# Tempatroller.net
KiCad netlist of a schematic drawn in EAGLE
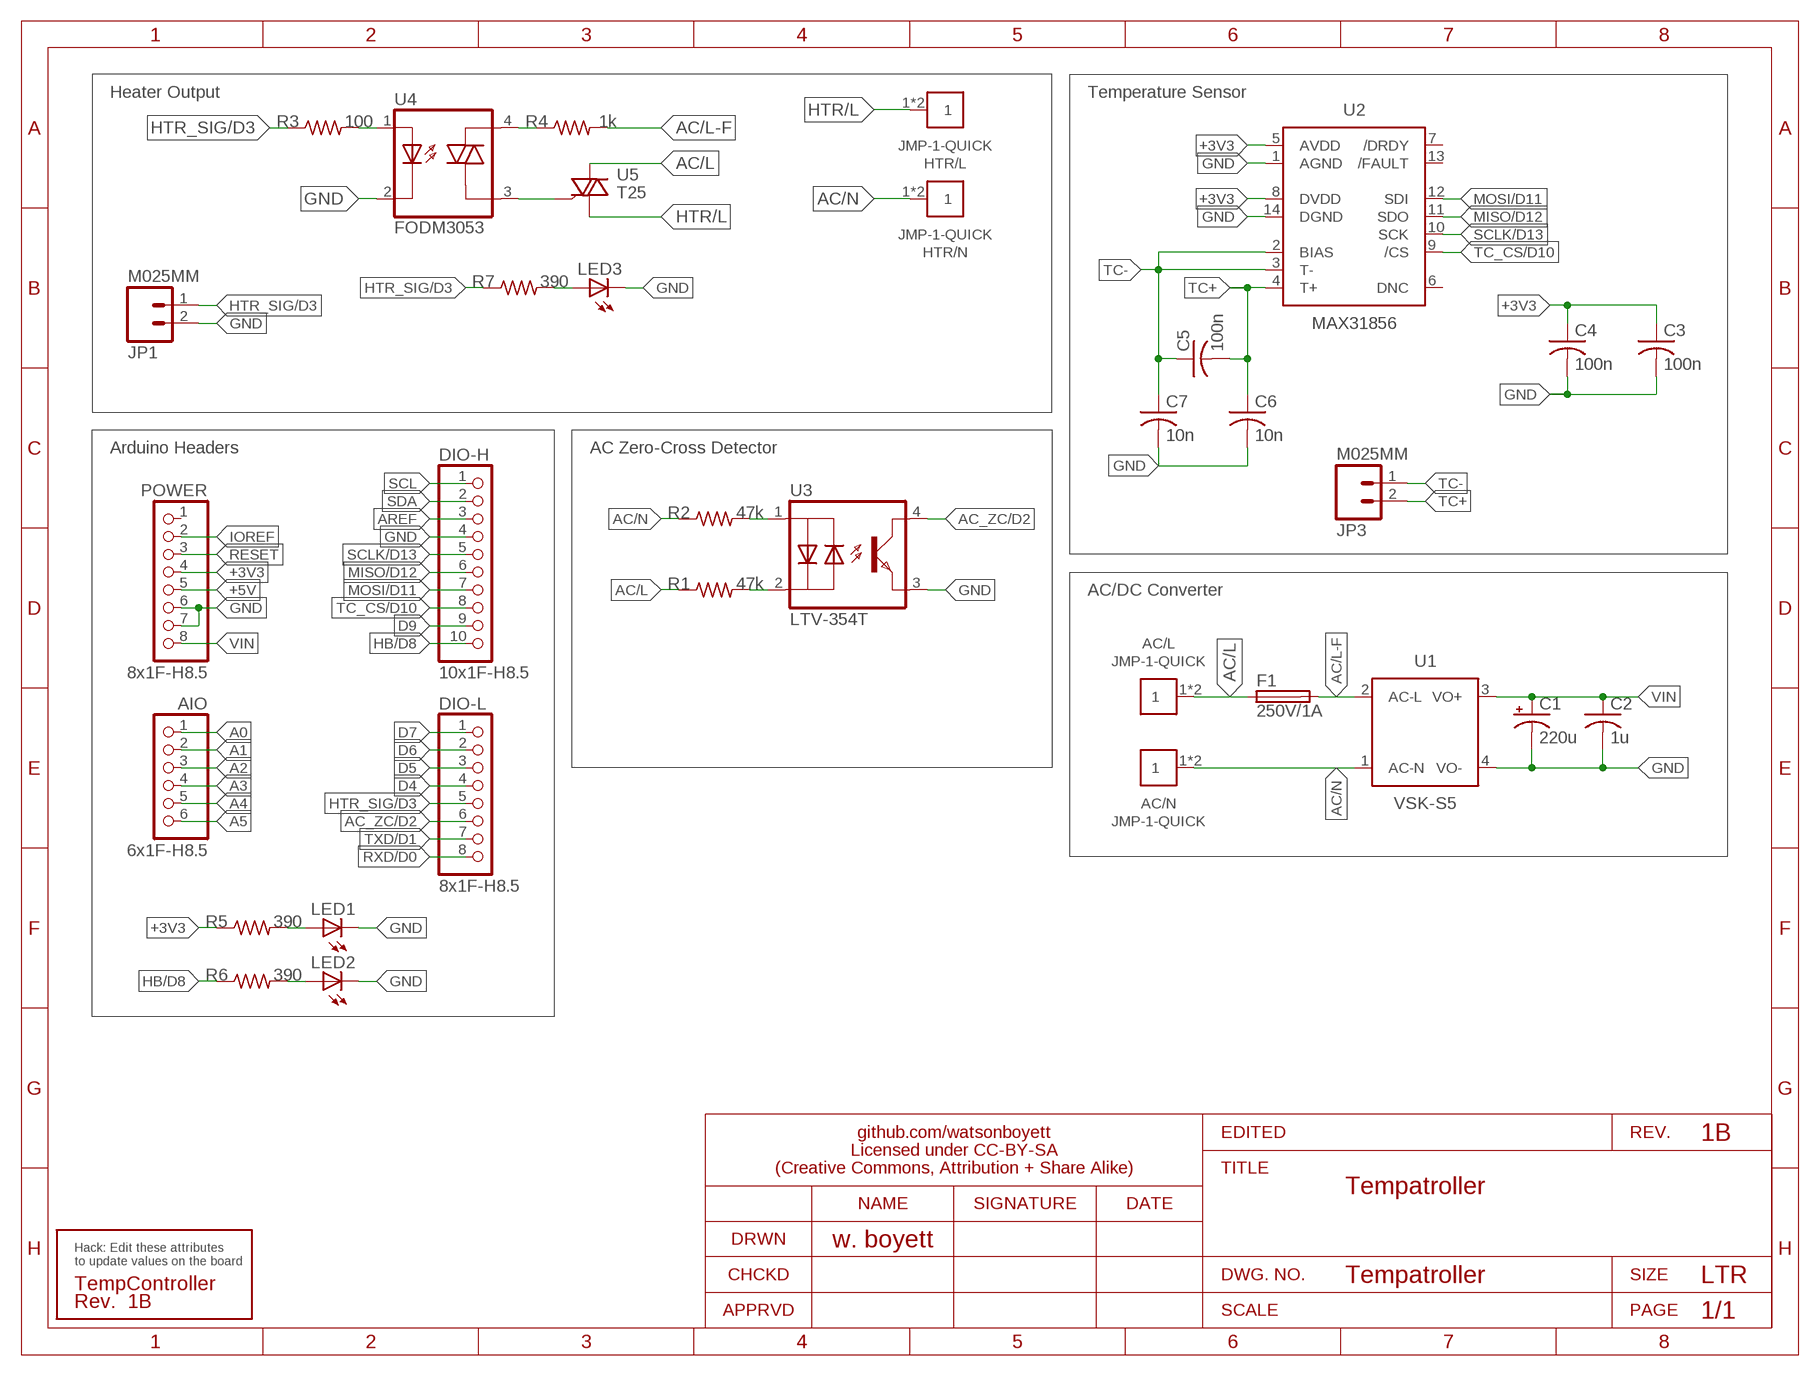
[diagram p0: schematic, sheet 1]

(export (version "E")
  (design (tool "Eeschema 10.0.6"))
  (components
    (comp (ref "AC/L")
      (value "JMP-1-QUICK")
      (footprint "eagle-import:QUICK-1")
      (fields (field (name "MPN") "1287"))
      (libsource (lib "eagle-import") (part "JMP-1-QUICK"))
    )
    (comp (ref "AC/N")
      (value "JMP-1-QUICK")
      (footprint "eagle-import:QUICK-1")
      (fields (field (name "MPN") "1287"))
      (libsource (lib "eagle-import") (part "JMP-1-QUICK"))
    )
    (comp (ref "AIO")
      (value "6x1F-H8.5")
      (footprint "eagle-import:1X06")
      (libsource (lib "eagle-import") (part "PINHD-1X6TH"))
    )
    (comp (ref "C1")
      (value "220u")
      (footprint "eagle-import:153CLV-1014")
      (libsource (lib "eagle-import") (part "CPOL-US153CLV-1014"))
    )
    (comp (ref "C2")
      (value "1u")
      (footprint "eagle-import:C0805")
      (libsource (lib "eagle-import") (part "C-USC0805"))
    )
    (comp (ref "C3")
      (value "100n")
      (footprint "eagle-import:C0805")
      (libsource (lib "eagle-import") (part "C-USC0805"))
    )
    (comp (ref "C4")
      (value "100n")
      (footprint "eagle-import:C0805")
      (libsource (lib "eagle-import") (part "C-USC0805"))
    )
    (comp (ref "C5")
      (value "100n")
      (footprint "eagle-import:C0805")
      (libsource (lib "eagle-import") (part "C-USC0805"))
    )
    (comp (ref "C6")
      (value "10n")
      (footprint "eagle-import:C0805")
      (libsource (lib "eagle-import") (part "C-USC0805"))
    )
    (comp (ref "C7")
      (value "10n")
      (footprint "eagle-import:C0805")
      (libsource (lib "eagle-import") (part "C-USC0805"))
    )
    (comp (ref "DIO-H")
      (value "10x1F-H8.5")
      (footprint "eagle-import:1X10")
      (libsource (lib "eagle-import") (part "PINHD-1X10TH"))
    )
    (comp (ref "DIO-L")
      (value "8x1F-H8.5")
      (footprint "eagle-import:1X08")
      (libsource (lib "eagle-import") (part "PINHD-1X8TH"))
    )
    (comp (ref "F1")
      (value "250V/1A")
      (footprint "eagle-import:2SMD-2410")
      (fields
        (field (name "MPN") "0452004.MRL")
        (field (name "MPN_1") "0454001.MR")
        (field (name "PN-DK") "F3144CT-ND")
      )
      (libsource (lib "eagle-import") (part "FUSE2410"))
    )
    (comp (ref "HTR/L")
      (value "JMP-1-QUICK")
      (footprint "eagle-import:QUICK-1")
      (fields (field (name "MPN") "1287"))
      (libsource (lib "eagle-import") (part "JMP-1-QUICK"))
    )
    (comp (ref "HTR/N")
      (value "JMP-1-QUICK")
      (footprint "eagle-import:QUICK-1")
      (fields (field (name "MPN") "1287"))
      (libsource (lib "eagle-import") (part "JMP-1-QUICK"))
    )
    (comp (ref "JP1")
      (value "M025MM")
      (footprint "eagle-import:SCREWTERMINAL-5MM-2")
      (fields (field (name "MPN") "1729128"))
      (libsource (lib "eagle-import") (part "M025MM"))
    )
    (comp (ref "JP3")
      (value "M025MM")
      (footprint "eagle-import:SCREWTERMINAL-5MM-2")
      (fields (field (name "MPN") "1729128"))
      (libsource (lib "eagle-import") (part "M025MM"))
    )
    (comp (ref "LED1")
      (value "LEDCHIP-LED0805")
      (footprint "eagle-import:CHIP-LED0805")
      (fields (field (name "MPN") "SML-LXT0805IW-TR"))
      (libsource (lib "eagle-import") (part "LEDCHIP-LED0805"))
    )
    (comp (ref "LED2")
      (value "LEDCHIP-LED0805")
      (footprint "eagle-import:CHIP-LED0805")
      (fields (field (name "MPN") "SML-LXT0805IW-TR"))
      (libsource (lib "eagle-import") (part "LEDCHIP-LED0805"))
    )
    (comp (ref "LED3")
      (value "LEDCHIP-LED0805")
      (footprint "eagle-import:CHIP-LED0805")
      (fields (field (name "MPN") "SML-LXT0805IW-TR"))
      (libsource (lib "eagle-import") (part "LEDCHIP-LED0805"))
    )
    (comp (ref "POWER")
      (value "8x1F-H8.5")
      (footprint "eagle-import:1X08")
      (libsource (lib "eagle-import") (part "PINHD-1X8TH"))
    )
    (comp (ref "R1")
      (value "47k")
      (footprint "eagle-import:R1206")
      (libsource (lib "eagle-import") (part "R-US_R1206"))
    )
    (comp (ref "R2")
      (value "47k")
      (footprint "eagle-import:R1206")
      (libsource (lib "eagle-import") (part "R-US_R1206"))
    )
    (comp (ref "R3")
      (value "100")
      (footprint "eagle-import:R0805")
      (libsource (lib "eagle-import") (part "R-US_R0805"))
    )
    (comp (ref "R4")
      (value "1k")
      (footprint "eagle-import:R1206")
      (libsource (lib "eagle-import") (part "R-US_R1206"))
    )
    (comp (ref "R5")
      (value "390")
      (footprint "eagle-import:R0805")
      (libsource (lib "eagle-import") (part "R-US_R0805"))
    )
    (comp (ref "R6")
      (value "390")
      (footprint "eagle-import:R0805")
      (libsource (lib "eagle-import") (part "R-US_R0805"))
    )
    (comp (ref "R7")
      (value "390")
      (footprint "eagle-import:R0805")
      (libsource (lib "eagle-import") (part "R-US_R0805"))
    )
    (comp (ref "U$1")
      (value "SILK_QC")
      (footprint "eagle-import:SILK_QC")
      (fields (field (name "MPN") "DNP") (field (name "PRODUCT") "TempController") (field (name "REV") "1B"))
      (libsource (lib "eagle-import") (part "SILK_QC"))
    )
    (comp (ref "U1")
      (value "VSK-S5")
      (footprint "eagle-import:VSK-S5")
      (libsource (lib "eagle-import") (part "VSK-S5"))
    )
    (comp (ref "U2")
      (value "MAX31856")
      (footprint "eagle-import:TSSOP14")
      (fields (field (name "MPN") "MAX31856MUD+"))
      (libsource (lib "eagle-import") (part "MAX31856"))
    )
    (comp (ref "U3")
      (value "LTV-354T")
      (footprint "eagle-import:SOP-4")
      (libsource (lib "eagle-import") (part "LTV-354T"))
    )
    (comp (ref "U4")
      (value "FODM3053")
      (footprint "eagle-import:SOP-4")
      (fields (field (name "MPN") "FODM3053R2_NF098"))
      (libsource (lib "eagle-import") (part "FODM3053"))
    )
    (comp (ref "U5")
      (value "T25")
      (footprint "eagle-import:TO263-3")
      (libsource (lib "eagle-import") (part "T835-TO263"))
    )
  )
  (nets
    (net (code "1") (name "+3V3") (class "Default")
      (node (ref "C3") (pin "1") (pinfunction "1_1") (pintype "passive"))
      (node (ref "C4") (pin "1") (pinfunction "1_1") (pintype "passive"))
      (node (ref "POWER") (pin "4") (pinfunction "4_4") (pintype "passive"))
      (node (ref "R5") (pin "1") (pinfunction "1_1") (pintype "passive"))
      (node (ref "U2") (pin "5") (pinfunction "AVDD_5") (pintype "power_in"))
      (node (ref "U2") (pin "8") (pinfunction "DVDD_8") (pintype "power_in"))
    )
    (net (code "2") (name "+5V") (class "Default")
      (node (ref "POWER") (pin "5") (pinfunction "5_5") (pintype "passive"))
    )
    (net (code "3") (name "A0") (class "Default")
      (node (ref "AIO") (pin "1") (pinfunction "1_1") (pintype "passive"))
    )
    (net (code "4") (name "A1") (class "Default")
      (node (ref "AIO") (pin "2") (pinfunction "2_2") (pintype "passive"))
    )
    (net (code "5") (name "A2") (class "Default")
      (node (ref "AIO") (pin "3") (pinfunction "3_3") (pintype "passive"))
    )
    (net (code "6") (name "A3") (class "Default")
      (node (ref "AIO") (pin "4") (pinfunction "4_4") (pintype "passive"))
    )
    (net (code "7") (name "A4") (class "Default")
      (node (ref "AIO") (pin "5") (pinfunction "5_5") (pintype "passive"))
    )
    (net (code "8") (name "A5") (class "Default")
      (node (ref "AIO") (pin "6") (pinfunction "6_6") (pintype "passive"))
    )
    (net (code "9") (name "AC_ZC{slash}D2") (class "Default")
      (node (ref "DIO-L") (pin "6") (pinfunction "6_6") (pintype "passive"))
      (node (ref "U3") (pin "4") (pinfunction "COL_4") (pintype "passive"))
    )
    (net (code "10") (name "AC{slash}L") (class "Default")
      (node (ref "AC/L") (pin "1") (pinfunction "1_1") (pintype "bidirectional"))
      (node (ref "AC/L") (pin "2") (pinfunction "1_2") (pintype "bidirectional"))
      (node (ref "F1") (pin "P$1") (pinfunction "1_P$1") (pintype "passive"))
      (node (ref "R1") (pin "1") (pinfunction "1_1") (pintype "passive"))
      (node (ref "U5") (pin "3") (pinfunction "A2_3") (pintype "passive"))
    )
    (net (code "11") (name "AC{slash}L-F") (class "Default")
      (node (ref "F1") (pin "P$2") (pinfunction "2_P$2") (pintype "passive"))
      (node (ref "R4") (pin "2") (pinfunction "2_2") (pintype "passive"))
      (node (ref "U1") (pin "2") (pinfunction "AC-L_2") (pintype "passive"))
    )
    (net (code "12") (name "AC{slash}N") (class "Default")
      (node (ref "AC/N") (pin "1") (pinfunction "1_1") (pintype "bidirectional"))
      (node (ref "AC/N") (pin "2") (pinfunction "1_2") (pintype "bidirectional"))
      (node (ref "HTR/N") (pin "1") (pinfunction "1_1") (pintype "bidirectional"))
      (node (ref "HTR/N") (pin "2") (pinfunction "1_2") (pintype "bidirectional"))
      (node (ref "R2") (pin "1") (pinfunction "1_1") (pintype "passive"))
      (node (ref "U1") (pin "1") (pinfunction "AC-N_1") (pintype "passive"))
    )
    (net (code "13") (name "AREF") (class "Default")
      (node (ref "DIO-H") (pin "3") (pinfunction "3_3") (pintype "passive"))
    )
    (net (code "14") (name "D4") (class "Default")
      (node (ref "DIO-L") (pin "4") (pinfunction "4_4") (pintype "passive"))
    )
    (net (code "15") (name "D5") (class "Default")
      (node (ref "DIO-L") (pin "3") (pinfunction "3_3") (pintype "passive"))
    )
    (net (code "16") (name "D6") (class "Default")
      (node (ref "DIO-L") (pin "2") (pinfunction "2_2") (pintype "passive"))
    )
    (net (code "17") (name "D7") (class "Default")
      (node (ref "DIO-L") (pin "1") (pinfunction "1_1") (pintype "passive"))
    )
    (net (code "18") (name "D9") (class "Default")
      (node (ref "DIO-H") (pin "9") (pinfunction "9_9") (pintype "passive"))
    )
    (net (code "19") (name "GND") (class "Default")
      (node (ref "C1") (pin "-") (pinfunction "-_-") (pintype "passive"))
      (node (ref "C2") (pin "2") (pinfunction "2_2") (pintype "passive"))
      (node (ref "C3") (pin "2") (pinfunction "2_2") (pintype "passive"))
      (node (ref "C4") (pin "2") (pinfunction "2_2") (pintype "passive"))
      (node (ref "C6") (pin "2") (pinfunction "2_2") (pintype "passive"))
      (node (ref "C7") (pin "2") (pinfunction "2_2") (pintype "passive"))
      (node (ref "DIO-H") (pin "4") (pinfunction "4_4") (pintype "passive"))
      (node (ref "JP1") (pin "2") (pinfunction "2_2") (pintype "passive"))
      (node (ref "LED1") (pin "C") (pinfunction "C_C") (pintype "passive"))
      (node (ref "LED2") (pin "C") (pinfunction "C_C") (pintype "passive"))
      (node (ref "LED3") (pin "C") (pinfunction "C_C") (pintype "passive"))
      (node (ref "POWER") (pin "6") (pinfunction "6_6") (pintype "passive"))
      (node (ref "POWER") (pin "7") (pinfunction "7_7") (pintype "passive"))
      (node (ref "U1") (pin "4") (pinfunction "VO-_4") (pintype "passive"))
      (node (ref "U2") (pin "1") (pinfunction "AGND_1") (pintype "power_in"))
      (node (ref "U2") (pin "14") (pinfunction "DGND_14") (pintype "power_in"))
      (node (ref "U3") (pin "3") (pinfunction "EMIT_3") (pintype "passive"))
      (node (ref "U4") (pin "2") (pinfunction "C_2") (pintype "passive"))
    )
    (net (code "20") (name "HB{slash}D8") (class "Default")
      (node (ref "DIO-H") (pin "10") (pinfunction "10_10") (pintype "passive"))
      (node (ref "R6") (pin "1") (pinfunction "1_1") (pintype "passive"))
    )
    (net (code "21") (name "HTR_SIG{slash}D3") (class "Default")
      (node (ref "DIO-L") (pin "5") (pinfunction "5_5") (pintype "passive"))
      (node (ref "JP1") (pin "1") (pinfunction "1_1") (pintype "passive"))
      (node (ref "R3") (pin "1") (pinfunction "1_1") (pintype "passive"))
      (node (ref "R7") (pin "1") (pinfunction "1_1") (pintype "passive"))
    )
    (net (code "22") (name "HTR{slash}L") (class "Default")
      (node (ref "HTR/L") (pin "1") (pinfunction "1_1") (pintype "bidirectional"))
      (node (ref "HTR/L") (pin "2") (pinfunction "1_2") (pintype "bidirectional"))
      (node (ref "U5") (pin "1") (pinfunction "A1_1") (pintype "passive"))
    )
    (net (code "23") (name "IOREF") (class "Default")
      (node (ref "POWER") (pin "2") (pinfunction "2_2") (pintype "passive"))
    )
    (net (code "24") (name "MISO{slash}D12") (class "Default")
      (node (ref "DIO-H") (pin "6") (pinfunction "6_6") (pintype "passive"))
      (node (ref "U2") (pin "11") (pinfunction "SDO_11") (pintype "bidirectional"))
    )
    (net (code "25") (name "MOSI{slash}D11") (class "Default")
      (node (ref "DIO-H") (pin "7") (pinfunction "7_7") (pintype "passive"))
      (node (ref "U2") (pin "12") (pinfunction "SDI_12") (pintype "bidirectional"))
    )
    (net (code "26") (name "Net-(LED1-PadA)") (class "Default")
      (node (ref "LED1") (pin "A") (pinfunction "A_A") (pintype "passive"))
      (node (ref "R5") (pin "2") (pinfunction "2_2") (pintype "passive"))
    )
    (net (code "27") (name "Net-(LED2-PadA)") (class "Default")
      (node (ref "LED2") (pin "A") (pinfunction "A_A") (pintype "passive"))
      (node (ref "R6") (pin "2") (pinfunction "2_2") (pintype "passive"))
    )
    (net (code "28") (name "Net-(LED3-PadA)") (class "Default")
      (node (ref "LED3") (pin "A") (pinfunction "A_A") (pintype "passive"))
      (node (ref "R7") (pin "2") (pinfunction "2_2") (pintype "passive"))
    )
    (net (code "29") (name "Net-(U3-A)") (class "Default")
      (node (ref "R2") (pin "2") (pinfunction "2_2") (pintype "passive"))
      (node (ref "U3") (pin "1") (pinfunction "A_1") (pintype "passive"))
    )
    (net (code "30") (name "Net-(U3-C)") (class "Default")
      (node (ref "R1") (pin "2") (pinfunction "2_2") (pintype "passive"))
      (node (ref "U3") (pin "2") (pinfunction "C_2") (pintype "passive"))
    )
    (net (code "31") (name "Net-(U4-A)") (class "Default")
      (node (ref "R3") (pin "2") (pinfunction "2_2") (pintype "passive"))
      (node (ref "U4") (pin "1") (pinfunction "A_1") (pintype "passive"))
    )
    (net (code "32") (name "Net-(U4-A1)") (class "Default")
      (node (ref "U4") (pin "3") (pinfunction "A1_3") (pintype "passive"))
      (node (ref "U5") (pin "2") (pinfunction "G_2") (pintype "passive"))
    )
    (net (code "33") (name "Net-(U4-A2)") (class "Default")
      (node (ref "R4") (pin "1") (pinfunction "1_1") (pintype "passive"))
      (node (ref "U4") (pin "4") (pinfunction "A2_4") (pintype "passive"))
    )
    (net (code "34") (name "RESET") (class "Default")
      (node (ref "POWER") (pin "3") (pinfunction "3_3") (pintype "passive"))
    )
    (net (code "35") (name "RXD{slash}D0") (class "Default")
      (node (ref "DIO-L") (pin "8") (pinfunction "8_8") (pintype "passive"))
    )
    (net (code "36") (name "SCL") (class "Default")
      (node (ref "DIO-H") (pin "1") (pinfunction "1_1") (pintype "passive"))
    )
    (net (code "37") (name "SCLK{slash}D13") (class "Default")
      (node (ref "DIO-H") (pin "5") (pinfunction "5_5") (pintype "passive"))
      (node (ref "U2") (pin "10") (pinfunction "SCK_10") (pintype "bidirectional"))
    )
    (net (code "38") (name "SDA") (class "Default")
      (node (ref "DIO-H") (pin "2") (pinfunction "2_2") (pintype "passive"))
    )
    (net (code "39") (name "TC+") (class "Default")
      (node (ref "C5") (pin "2") (pinfunction "2_2") (pintype "passive"))
      (node (ref "C6") (pin "1") (pinfunction "1_1") (pintype "passive"))
      (node (ref "JP3") (pin "2") (pinfunction "2_2") (pintype "passive"))
      (node (ref "U2") (pin "4") (pinfunction "T+_4") (pintype "bidirectional"))
    )
    (net (code "40") (name "TC-") (class "Default")
      (node (ref "C5") (pin "1") (pinfunction "1_1") (pintype "passive"))
      (node (ref "C7") (pin "1") (pinfunction "1_1") (pintype "passive"))
      (node (ref "JP3") (pin "1") (pinfunction "1_1") (pintype "passive"))
      (node (ref "U2") (pin "2") (pinfunction "BIAS_2") (pintype "bidirectional"))
      (node (ref "U2") (pin "3") (pinfunction "T-_3") (pintype "bidirectional"))
    )
    (net (code "41") (name "TC_CS{slash}D10") (class "Default")
      (node (ref "DIO-H") (pin "8") (pinfunction "8_8") (pintype "passive"))
      (node (ref "U2") (pin "9") (pinfunction "/CS_9") (pintype "bidirectional"))
    )
    (net (code "42") (name "TXD{slash}D1") (class "Default")
      (node (ref "DIO-L") (pin "7") (pinfunction "7_7") (pintype "passive"))
    )
    (net (code "43") (name "VIN") (class "Default")
      (node (ref "C1") (pin "+") (pinfunction "+_+") (pintype "passive"))
      (node (ref "C2") (pin "1") (pinfunction "1_1") (pintype "passive"))
      (node (ref "POWER") (pin "8") (pinfunction "8_8") (pintype "passive"))
      (node (ref "U1") (pin "3") (pinfunction "VO+_3") (pintype "passive"))
    )
    (net (code "44") (name "unconnected-(POWER-Pad1)") (class "Default")
      (node (ref "POWER") (pin "1") (pinfunction "1_1") (pintype "passive"))
    )
    (net (code "45") (name "unconnected-(U2-DNC-Pad6)") (class "Default")
      (node (ref "U2") (pin "6") (pinfunction "DNC_6") (pintype "no_connect"))
    )
    (net (code "46") (name "unconnected-(U2-{slash}DRDY-Pad7)") (class "Default")
      (node (ref "U2") (pin "7") (pinfunction "/DRDY_7") (pintype "bidirectional"))
    )
    (net (code "47") (name "unconnected-(U2-{slash}FAULT-Pad13)") (class "Default")
      (node (ref "U2") (pin "13") (pinfunction "/FAULT_13") (pintype "bidirectional"))
    )
  )
)
